# convertisseur3V3.net
KiCad netlist of a schematic drawn in EAGLE
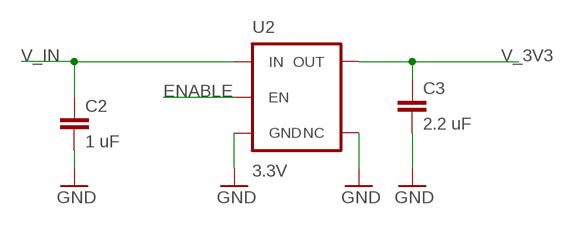
[diagram p0: schematic, sheet 1]

(export (version "E")
  (design (tool "Eeschema 10.0.6"))
  (components
    (comp (ref "C2")
      (value "1 uF")
      (footprint "eagle-import:1206")
      (libsource (lib "eagle-import") (part "CAP1206"))
    )
    (comp (ref "C3")
      (value "2.2 uF")
      (footprint "eagle-import:1206")
      (libsource (lib "eagle-import") (part "CAP1206"))
    )
    (comp (ref "U2")
      (value "3.3V")
      (footprint "eagle-import:SOT23-5")
      (libsource (lib "eagle-import") (part "V_REG_AP2112K-3.3V"))
    )
  )
  (nets
    (net (code "1") (name "/ENABLE") (class "Default")
      (node (ref "U2") (pin "3") (pinfunction "EN_3") (pintype "input"))
    )
    (net (code "2") (name "/V_3V3") (class "Default")
      (node (ref "C3") (pin "1") (pinfunction "1_1") (pintype "passive"))
      (node (ref "U2") (pin "5") (pinfunction "OUT_5") (pintype "passive"))
    )
    (net (code "3") (name "/V_IN") (class "Default")
      (node (ref "C2") (pin "1") (pinfunction "1_1") (pintype "passive"))
      (node (ref "U2") (pin "1") (pinfunction "IN_1") (pintype "input"))
    )
    (net (code "4") (name "GND") (class "Default")
      (node (ref "C2") (pin "2") (pinfunction "2_2") (pintype "passive"))
      (node (ref "C3") (pin "2") (pinfunction "2_2") (pintype "passive"))
      (node (ref "U2") (pin "2") (pinfunction "GND_2") (pintype "input"))
      (node (ref "U2") (pin "4") (pinfunction "NC_4") (pintype "input"))
    )
  )
)
